# PROC051D_Tempsensor.net
KiCad netlist of a schematic drawn in Altium Designer
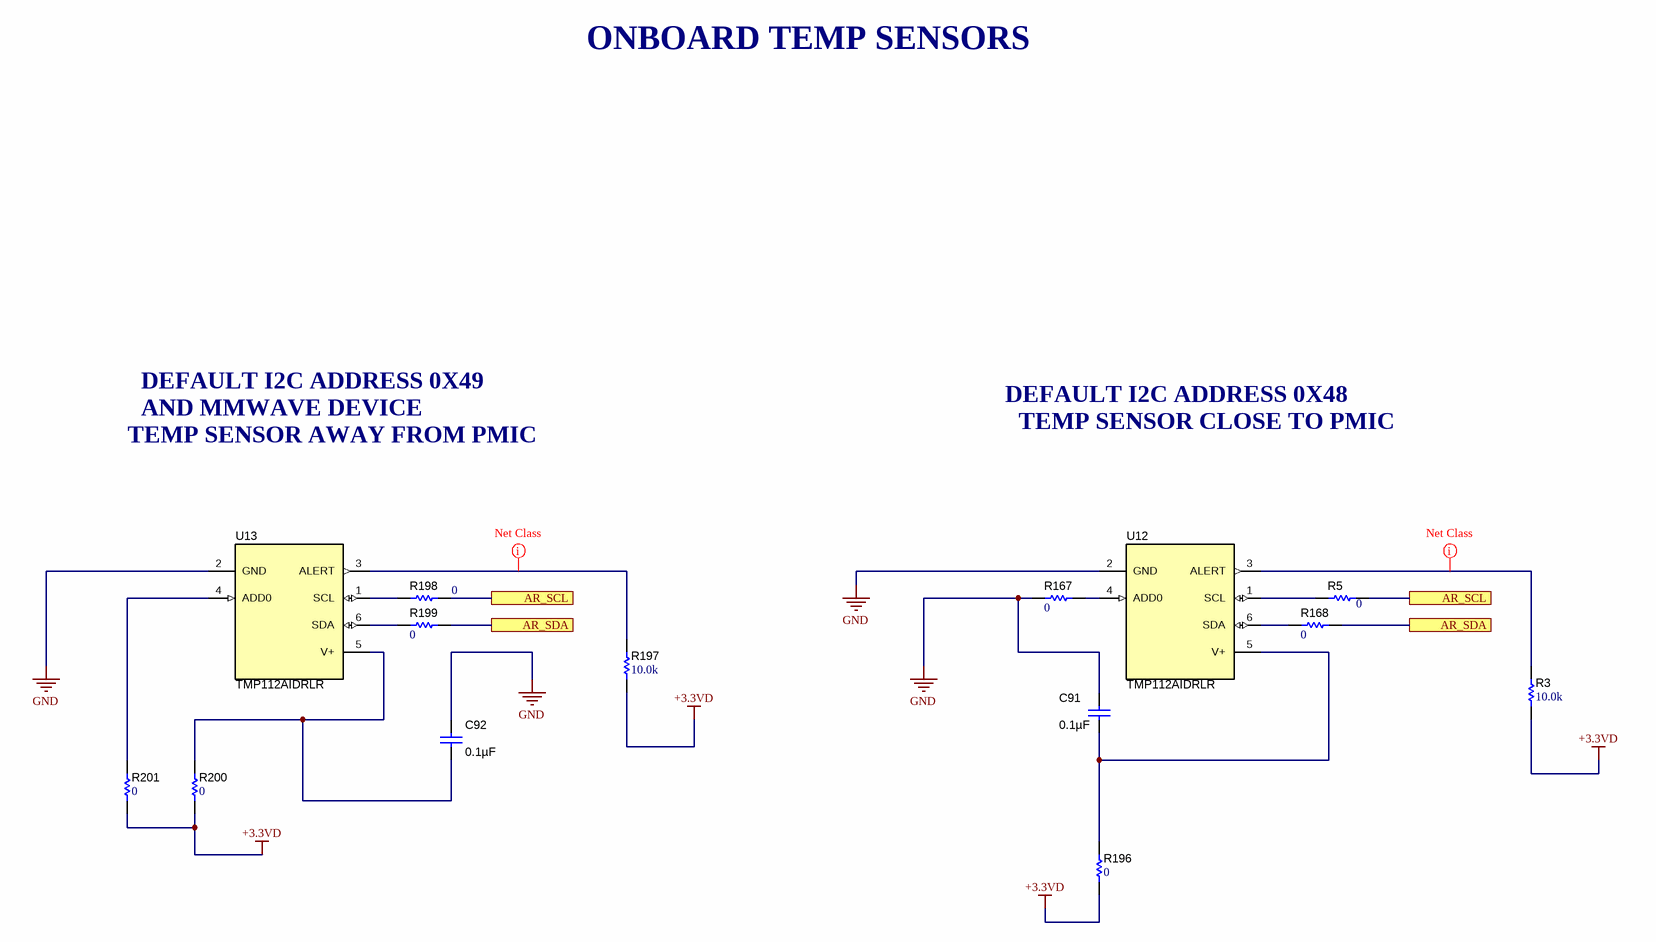
[diagram p0: PROC051D_Tempsensor.SchDoc]

(export (version "E")
  (design (tool "Eeschema 10.0.6"))
  (components
    (comp (ref "C91")
      (value "C0402C104K8RACTU")
      (footprint "0402L")
      (description "CAP, CERM, 0.1 µF, 10 V,+/- 10%, X7R, 0402")
      (fields (field (name "MANUFACTURER") "Kemet") (field (name "VALUEDISPLAYED") "0.1µF"))
      (libsource (lib "Altium Vault - TI") (part "Capacitor"))
    )
    (comp (ref "C92")
      (value "C0402C104K8RACTU")
      (footprint "0402L")
      (description "CAP, CERM, 0.1 µF, 10 V,+/- 10%, X7R, 0402")
      (fields (field (name "MANUFACTURER") "Kemet") (field (name "VALUEDISPLAYED") "0.1µF"))
      (libsource (lib "Altium Vault - TI") (part "Capacitor"))
    )
    (comp (ref "R3")
      (value "CRCW040210K0FKED")
      (footprint "0402L")
      (description "RES, 10.0 k, 1%, 0.063 W, AEC-Q200 Grade 0, 0402")
      (fields (field (name "MANUFACTURER") "Vishay-Dale") (field (name "VALUEDISPLAYED") "10.0k"))
      (libsource (lib "Altium Vault - TI") (part "Resistor"))
    )
    (comp (ref "R5")
      (value "CRCW02010000Z0ED")
      (footprint "0201_Silk")
      (description "RES, 0, 5%, 0.05 W, 0201")
      (fields (field (name "MANUFACTURER") "Vishay-Dale") (field (name "VALUEDISPLAYED") "0"))
      (libsource (lib "Altium Vault - TI") (part "Resistor"))
    )
    (comp (ref "R167")
      (value "CRCW02010000Z0ED")
      (footprint "0201_Silk")
      (description "RES, 0, 5%, 0.05 W, 0201")
      (fields (field (name "MANUFACTURER") "Vishay-Dale") (field (name "VALUEDISPLAYED") "0"))
      (libsource (lib "Altium Vault - TI") (part "Resistor"))
    )
    (comp (ref "R168")
      (value "CRCW02010000Z0ED")
      (footprint "0201_Silk")
      (description "RES, 0, 5%, 0.05 W, 0201")
      (fields (field (name "MANUFACTURER") "Vishay-Dale") (field (name "VALUEDISPLAYED") "0"))
      (libsource (lib "Altium Vault - TI") (part "Resistor"))
    )
    (comp (ref "R196")
      (value "ERJ-2GE0R00X")
      (footprint "0402L")
      (description "RES, 0, 5%, 0.1 W, AEC-Q200 Grade 0, 0402")
      (fields (field (name "MANUFACTURER") "Panasonic") (field (name "VALUEDISPLAYED") "0"))
      (libsource (lib "Altium Vault - TI") (part "Resistor"))
    )
    (comp (ref "R197")
      (value "CRCW040210K0FKED")
      (footprint "0402L")
      (description "RES, 10.0 k, 1%, 0.063 W, AEC-Q200 Grade 0, 0402")
      (fields (field (name "MANUFACTURER") "Vishay-Dale") (field (name "VALUEDISPLAYED") "10.0k"))
      (libsource (lib "Altium Vault - TI") (part "Resistor"))
    )
    (comp (ref "R198")
      (value "CRCW02010000Z0ED")
      (footprint "0201_Silk")
      (description "RES, 0, 5%, 0.05 W, 0201")
      (fields (field (name "MANUFACTURER") "Vishay-Dale") (field (name "VALUEDISPLAYED") "0"))
      (libsource (lib "Altium Vault - TI") (part "Resistor"))
    )
    (comp (ref "R199")
      (value "CRCW02010000Z0ED")
      (footprint "0201_Silk")
      (description "RES, 0, 5%, 0.05 W, 0201")
      (fields (field (name "MANUFACTURER") "Vishay-Dale") (field (name "VALUEDISPLAYED") "0"))
      (libsource (lib "Altium Vault - TI") (part "Resistor"))
    )
    (comp (ref "R200")
      (value "ERJ-2GE0R00X")
      (footprint "0402L")
      (description "RES, 0, 5%, 0.1 W, AEC-Q200 Grade 0, 0402")
      (fields (field (name "MANUFACTURER") "Panasonic") (field (name "VALUEDISPLAYED") "0"))
      (libsource (lib "Altium Vault - TI") (part "Resistor"))
    )
    (comp (ref "R201")
      (value "CRCW02010000Z0ED")
      (footprint "0201_Silk")
      (description "RES, 0, 5%, 0.05 W, 0201")
      (fields (field (name "MANUFACTURER") "Vishay-Dale") (field (name "VALUEDISPLAYED") "0"))
      (libsource (lib "Altium Vault - TI") (part "Resistor"))
    )
    (comp (ref "U12")
      (value "TMP112AIDRLR")
      (footprint "DRL0006A")
      (fields
        (field (name "ALTERNATE PARTNUMBER") "TMP112AIDRLT")
        (field (name "MANUFACTURER") "Texas Instruments")
        (field (name "PARTNUMBER") "TMP112AIDRLR")
        (field (name "PUBLISHER") "Texas Instruments")
      )
      (libsource (lib "Altium Vault - TI") (part "TMP112"))
    )
    (comp (ref "U13")
      (value "TMP112AIDRLR")
      (footprint "DRL0006A")
      (fields
        (field (name "ALTERNATE PARTNUMBER") "TMP112AIDRLT")
        (field (name "MANUFACTURER") "Texas Instruments")
        (field (name "PARTNUMBER") "TMP112AIDRLR")
        (field (name "PUBLISHER") "Texas Instruments")
      )
      (libsource (lib "Altium Vault - TI") (part "TMP112"))
    )
  )
  (nets
    (net (code "1") (name "+3.3VD") (class "Default")
      (node (ref "R196") (pin "2") (pinfunction "2_2") (pintype "passive"))
      (node (ref "R197") (pin "2") (pinfunction "2_2") (pintype "passive"))
      (node (ref "R200") (pin "2") (pinfunction "2_2") (pintype "passive"))
      (node (ref "R201") (pin "2") (pinfunction "2_2") (pintype "passive"))
      (node (ref "R3") (pin "2") (pinfunction "2_2") (pintype "passive"))
    )
    (net (code "2") (name "/AR_SCL") (class "Default")
      (node (ref "R198") (pin "1") (pinfunction "1_1") (pintype "passive"))
      (node (ref "R5") (pin "1") (pinfunction "1_1") (pintype "passive"))
    )
    (net (code "3") (name "/AR_SDA") (class "Default")
      (node (ref "R168") (pin "2") (pinfunction "2_2") (pintype "passive"))
      (node (ref "R199") (pin "2") (pinfunction "2_2") (pintype "passive"))
    )
    (net (code "4") (name "GND") (class "Default")
      (node (ref "C91") (pin "1") (pinfunction "1_1") (pintype "passive"))
      (node (ref "C92") (pin "1") (pinfunction "1_1") (pintype "passive"))
      (node (ref "R167") (pin "1") (pinfunction "1_1") (pintype "passive"))
      (node (ref "U12") (pin "2") (pinfunction "GND_2") (pintype "power_in"))
      (node (ref "U13") (pin "2") (pinfunction "GND_2") (pintype "power_in"))
    )
    (net (code "5") (name "Net-(U12-ADD0)") (class "Default")
      (node (ref "R167") (pin "2") (pinfunction "2_2") (pintype "passive"))
      (node (ref "U12") (pin "4") (pinfunction "ADD0_4") (pintype "input"))
    )
    (net (code "6") (name "Net-(U12-ALERT)") (class "Default")
      (node (ref "R3") (pin "1") (pinfunction "1_1") (pintype "passive"))
      (node (ref "U12") (pin "3") (pinfunction "ALERT_3") (pintype "output"))
    )
    (net (code "7") (name "Net-(U12-SCL)") (class "Default")
      (node (ref "R5") (pin "2") (pinfunction "2_2") (pintype "passive"))
      (node (ref "U12") (pin "1") (pinfunction "SCL_1") (pintype "bidirectional"))
    )
    (net (code "8") (name "Net-(U12-SDA)") (class "Default")
      (node (ref "R168") (pin "1") (pinfunction "1_1") (pintype "passive"))
      (node (ref "U12") (pin "6") (pinfunction "SDA_6") (pintype "bidirectional"))
    )
    (net (code "9") (name "Net-(U12-V+)") (class "Default")
      (node (ref "C91") (pin "2") (pinfunction "2_2") (pintype "passive"))
      (node (ref "R196") (pin "1") (pinfunction "1_1") (pintype "passive"))
      (node (ref "U12") (pin "5") (pinfunction "V+_5") (pintype "power_in"))
    )
    (net (code "10") (name "Net-(U13-ADD0)") (class "Default")
      (node (ref "R201") (pin "1") (pinfunction "1_1") (pintype "passive"))
      (node (ref "U13") (pin "4") (pinfunction "ADD0_4") (pintype "input"))
    )
    (net (code "11") (name "Net-(U13-ALERT)") (class "Default")
      (node (ref "R197") (pin "1") (pinfunction "1_1") (pintype "passive"))
      (node (ref "U13") (pin "3") (pinfunction "ALERT_3") (pintype "output"))
    )
    (net (code "12") (name "Net-(U13-SCL)") (class "Default")
      (node (ref "R198") (pin "2") (pinfunction "2_2") (pintype "passive"))
      (node (ref "U13") (pin "1") (pinfunction "SCL_1") (pintype "bidirectional"))
    )
    (net (code "13") (name "Net-(U13-SDA)") (class "Default")
      (node (ref "R199") (pin "1") (pinfunction "1_1") (pintype "passive"))
      (node (ref "U13") (pin "6") (pinfunction "SDA_6") (pintype "bidirectional"))
    )
    (net (code "14") (name "Net-(U13-V+)") (class "Default")
      (node (ref "C92") (pin "2") (pinfunction "2_2") (pintype "passive"))
      (node (ref "R200") (pin "1") (pinfunction "1_1") (pintype "passive"))
      (node (ref "U13") (pin "5") (pinfunction "V+_5") (pintype "power_in"))
    )
  )
)
